# design.net
KiCad netlist of a schematic drawn in Altium Designer
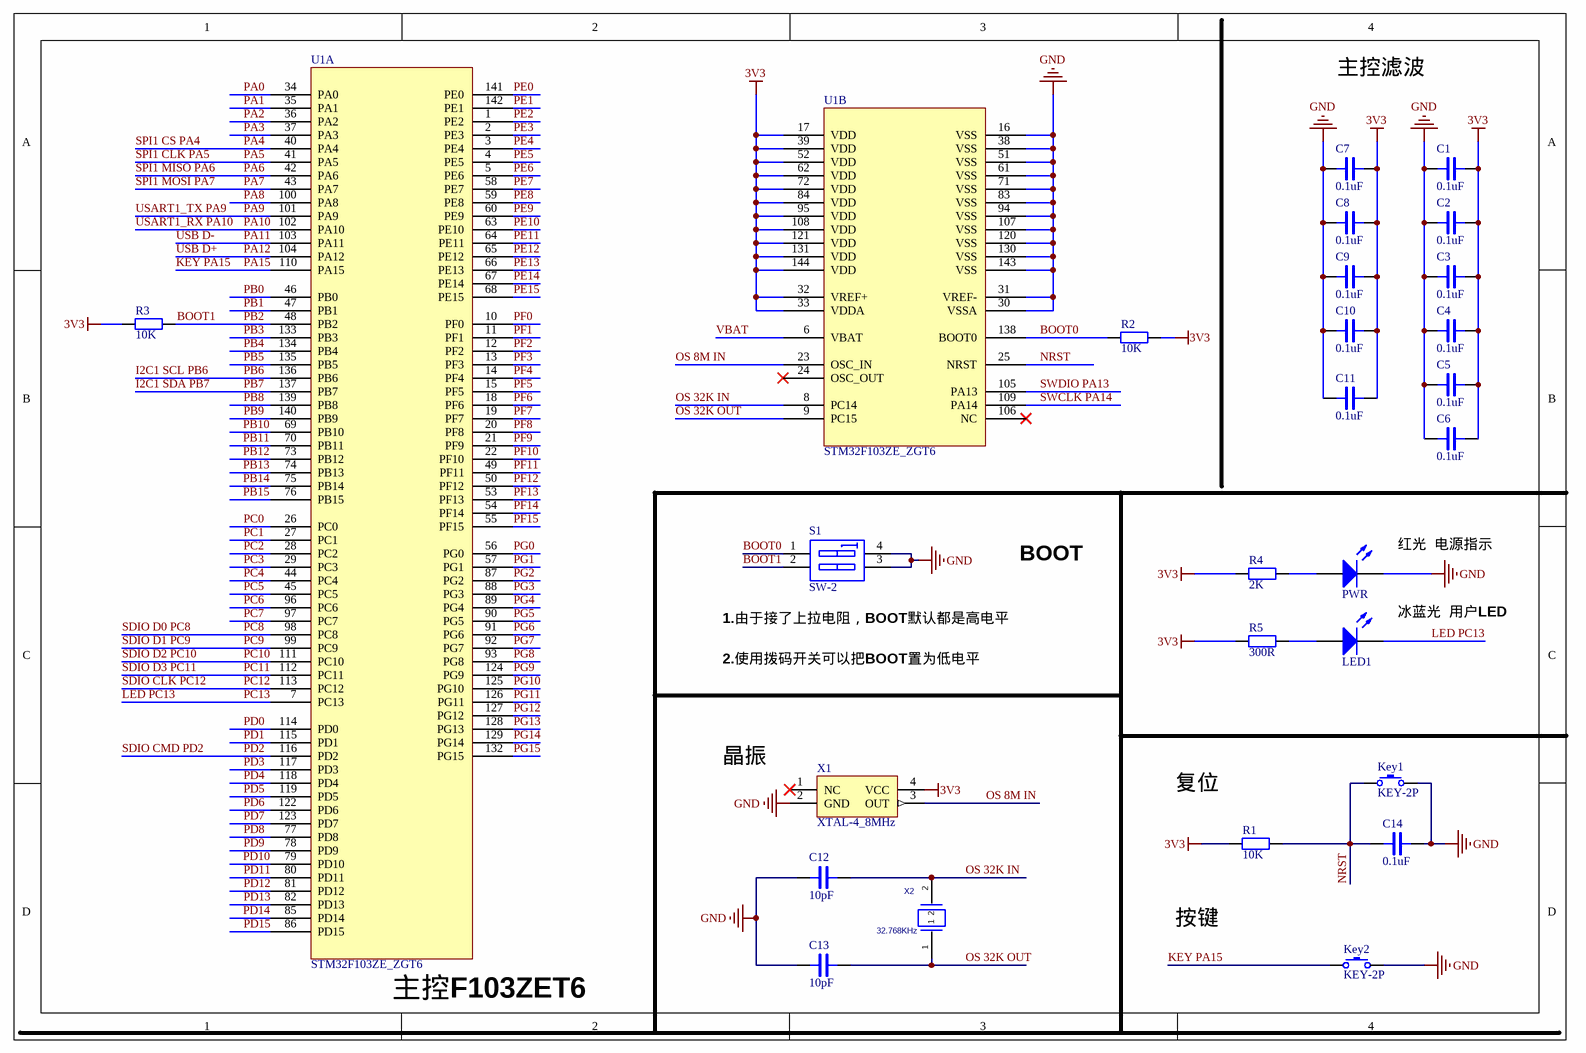
[diagram p0: 主控系统板.SchDoc]

(export (version "E")
  (design (tool "Eeschema 10.0.6"))
  (components
    (comp (ref "C1")
      (value "0.1uF")
      (footprint "0603")
      (description "Capacitor")
      (libsource (lib "General") (part "CAP"))
    )
    (comp (ref "C2")
      (value "0.1uF")
      (footprint "0603")
      (description "Capacitor")
      (libsource (lib "General") (part "CAP"))
    )
    (comp (ref "C3")
      (value "0.1uF")
      (footprint "0603")
      (description "Capacitor")
      (libsource (lib "General") (part "CAP"))
    )
    (comp (ref "C4")
      (value "0.1uF")
      (footprint "0603")
      (description "Capacitor")
      (libsource (lib "General") (part "CAP"))
    )
    (comp (ref "C5")
      (value "0.1uF")
      (footprint "0603")
      (description "Capacitor")
      (libsource (lib "General") (part "CAP"))
    )
    (comp (ref "C6")
      (value "0.1uF")
      (footprint "0603")
      (description "Capacitor")
      (libsource (lib "General") (part "CAP"))
    )
    (comp (ref "C7")
      (value "0.1uF")
      (footprint "0603")
      (description "Capacitor")
      (libsource (lib "General") (part "CAP"))
    )
    (comp (ref "C8")
      (value "0.1uF")
      (footprint "0603")
      (description "Capacitor")
      (libsource (lib "General") (part "CAP"))
    )
    (comp (ref "C9")
      (value "0.1uF")
      (footprint "0603")
      (description "Capacitor")
      (libsource (lib "General") (part "CAP"))
    )
    (comp (ref "C10")
      (value "0.1uF")
      (footprint "0603")
      (description "Capacitor")
      (libsource (lib "General") (part "CAP"))
    )
    (comp (ref "C11")
      (value "0.1uF")
      (footprint "0603")
      (description "Capacitor")
      (libsource (lib "General") (part "CAP"))
    )
    (comp (ref "C12")
      (value "10pF")
      (footprint "0603")
      (description "Capacitor")
      (libsource (lib "General") (part "CAP"))
    )
    (comp (ref "C13")
      (value "10pF")
      (footprint "0603")
      (description "Capacitor")
      (libsource (lib "General") (part "CAP"))
    )
    (comp (ref "C14")
      (value "0.1uF")
      (footprint "0603")
      (description "Capacitor")
      (libsource (lib "General") (part "CAP"))
    )
    (comp (ref "Key1")
      (value "KEY-2P")
      (footprint "TSW SMD-3*6*2.5")
      (description "Key")
      (libsource (lib "General") (part "KEY-2P"))
    )
    (comp (ref "Key2")
      (value "KEY-2P")
      (footprint "TSW SMD-3*6*2.5")
      (description "Key")
      (libsource (lib "General") (part "KEY-2P"))
    )
    (comp (ref "LED1")
      (value "LED")
      (footprint "D0603")
      (libsource (lib "altium-import") (part "root_0_LED_"))
    )
    (comp (ref "PWR")
      (value "LED")
      (footprint "D0603")
      (libsource (lib "altium-import") (part "root_0_LED_"))
    )
    (comp (ref "R1")
      (value "10K")
      (footprint "0603")
      (description "Resistor")
      (libsource (lib "") (part "RES_1"))
    )
    (comp (ref "R2")
      (value "10K")
      (footprint "0603")
      (description "Resistor")
      (libsource (lib "") (part "RES_1"))
    )
    (comp (ref "R3")
      (value "10K")
      (footprint "0603")
      (description "Resistor")
      (libsource (lib "General") (part "RES"))
    )
    (comp (ref "R4")
      (value "2K")
      (footprint "0603")
      (description "Resistor")
      (libsource (lib "General") (part "RES"))
    )
    (comp (ref "R5")
      (value "300R")
      (footprint "0603")
      (description "Resistor")
      (libsource (lib "General") (part "RES"))
    )
    (comp (ref "S1")
      (value "SW-2")
      (footprint "CSW1.27 SMD-2P")
      (libsource (lib "altium-import") (part "root_0_SW-2_"))
    )
    (comp (ref "U1")
      (value "STM32F103ZE_ZGT6")
      (footprint "TQFP144_N")
      (libsource (lib "altium-import") (part "root_0_STM32F103ZE_ZGT6_"))
    )
    (comp (ref "X1")
      (value "XTAL-4_8MHz")
      (footprint "XTAL-5.0X3.2")
      (description "Oscillator")
      (libsource (lib "General") (part "XTAL-4"))
    )
    (comp (ref "X2")
      (value "32.768KHz")
      (footprint "3215")
      (description "CRYSTAL")
      (fields (field (name "Comment") "XTAL_32.768KHZ_3215"))
      (libsource (lib "altium-import") (part "root_0_XTAL_32.768KHZ_3215_"))
    )
  )
  (nets
    (net (code "1") (name "/BOOT0") (class "Default")
      (node (ref "R2") (pin "1") (pinfunction "1_1") (pintype "passive"))
      (node (ref "S1") (pin "1") (pinfunction "A1_1") (pintype "passive"))
      (node (ref "U1") (pin "138") (pinfunction "BOOT0_138") (pintype "passive"))
    )
    (net (code "2") (name "/BOOT1") (class "Default")
      (node (ref "R3") (pin "1") (pinfunction "1_1") (pintype "passive"))
      (node (ref "S1") (pin "2") (pinfunction "A2_2") (pintype "passive"))
      (node (ref "U1") (pin "48") (pinfunction "PB2_48") (pintype "passive"))
    )
    (net (code "3") (name "/I2C1 SCL PB6") (class "Default")
      (node (ref "U1") (pin "136") (pinfunction "PB6_136") (pintype "passive"))
    )
    (net (code "4") (name "/I2C1 SDA PB7") (class "Default")
      (node (ref "U1") (pin "137") (pinfunction "PB7_137") (pintype "passive"))
    )
    (net (code "5") (name "/KEY PA15") (class "Default")
      (node (ref "Key2") (pin "1") (pinfunction "1_1") (pintype "passive"))
      (node (ref "U1") (pin "110") (pinfunction "PA15_110") (pintype "passive"))
    )
    (net (code "6") (name "/LED PC13") (class "Default")
      (node (ref "LED1") (pin "2") (pinfunction "K_2") (pintype "passive"))
      (node (ref "U1") (pin "7") (pinfunction "PC13_7") (pintype "passive"))
    )
    (net (code "7") (name "/NRST") (class "Default")
      (node (ref "C14") (pin "2") (pinfunction "2_2") (pintype "passive"))
      (node (ref "Key1") (pin "1") (pinfunction "1_1") (pintype "passive"))
      (node (ref "R1") (pin "2") (pinfunction "2_2") (pintype "passive"))
      (node (ref "U1") (pin "25") (pinfunction "NRST_25") (pintype "passive"))
    )
    (net (code "8") (name "/OS 8M IN") (class "Default")
      (node (ref "U1") (pin "23") (pinfunction "OSC_IN_23") (pintype "passive"))
      (node (ref "X1") (pin "3") (pinfunction "OUT_3") (pintype "output"))
    )
    (net (code "9") (name "/OS 32K IN") (class "Default")
      (node (ref "C12") (pin "1") (pinfunction "1_1") (pintype "passive"))
      (node (ref "U1") (pin "8") (pinfunction "PC14_8") (pintype "passive"))
      (node (ref "X2") (pin "2") (pinfunction "2_2") (pintype "passive"))
    )
    (net (code "10") (name "/OS 32K OUT") (class "Default")
      (node (ref "C13") (pin "1") (pinfunction "1_1") (pintype "passive"))
      (node (ref "U1") (pin "9") (pinfunction "PC15_9") (pintype "passive"))
      (node (ref "X2") (pin "1") (pinfunction "1_1") (pintype "passive"))
    )
    (net (code "11") (name "/PA0") (class "Default")
      (node (ref "U1") (pin "34") (pinfunction "PA0_34") (pintype "passive"))
    )
    (net (code "12") (name "/PA1") (class "Default")
      (node (ref "U1") (pin "35") (pinfunction "PA1_35") (pintype "passive"))
    )
    (net (code "13") (name "/PA2") (class "Default")
      (node (ref "U1") (pin "36") (pinfunction "PA2_36") (pintype "passive"))
    )
    (net (code "14") (name "/PA3") (class "Default")
      (node (ref "U1") (pin "37") (pinfunction "PA3_37") (pintype "passive"))
    )
    (net (code "15") (name "/PA4") (class "Default")
      (node (ref "U1") (pin "40") (pinfunction "PA4_40") (pintype "passive"))
    )
    (net (code "16") (name "/PA5") (class "Default")
      (node (ref "U1") (pin "41") (pinfunction "PA5_41") (pintype "passive"))
    )
    (net (code "17") (name "/PA6") (class "Default")
      (node (ref "U1") (pin "42") (pinfunction "PA6_42") (pintype "passive"))
    )
    (net (code "18") (name "/PA7") (class "Default")
      (node (ref "U1") (pin "43") (pinfunction "PA7_43") (pintype "passive"))
    )
    (net (code "19") (name "/PA8") (class "Default")
      (node (ref "U1") (pin "100") (pinfunction "PA8_100") (pintype "passive"))
    )
    (net (code "20") (name "/PA9") (class "Default")
      (node (ref "U1") (pin "101") (pinfunction "PA9_101") (pintype "passive"))
    )
    (net (code "21") (name "/PA10") (class "Default")
      (node (ref "U1") (pin "102") (pinfunction "PA10_102") (pintype "passive"))
    )
    (net (code "22") (name "/PA11") (class "Default")
      (node (ref "U1") (pin "103") (pinfunction "PA11_103") (pintype "passive"))
    )
    (net (code "23") (name "/PA12") (class "Default")
      (node (ref "U1") (pin "104") (pinfunction "PA12_104") (pintype "passive"))
    )
    (net (code "24") (name "/PB0") (class "Default")
      (node (ref "U1") (pin "46") (pinfunction "PB0_46") (pintype "passive"))
    )
    (net (code "25") (name "/PB1") (class "Default")
      (node (ref "U1") (pin "47") (pinfunction "PB1_47") (pintype "passive"))
    )
    (net (code "26") (name "/PB3") (class "Default")
      (node (ref "U1") (pin "133") (pinfunction "PB3_133") (pintype "passive"))
    )
    (net (code "27") (name "/PB4") (class "Default")
      (node (ref "U1") (pin "134") (pinfunction "PB4_134") (pintype "passive"))
    )
    (net (code "28") (name "/PB5") (class "Default")
      (node (ref "U1") (pin "135") (pinfunction "PB5_135") (pintype "passive"))
    )
    (net (code "29") (name "/PB8") (class "Default")
      (node (ref "U1") (pin "139") (pinfunction "PB8_139") (pintype "passive"))
    )
    (net (code "30") (name "/PB9") (class "Default")
      (node (ref "U1") (pin "140") (pinfunction "PB9_140") (pintype "passive"))
    )
    (net (code "31") (name "/PB10") (class "Default")
      (node (ref "U1") (pin "69") (pinfunction "PB10_69") (pintype "passive"))
    )
    (net (code "32") (name "/PB11") (class "Default")
      (node (ref "U1") (pin "70") (pinfunction "PB11_70") (pintype "passive"))
    )
    (net (code "33") (name "/PB12") (class "Default")
      (node (ref "U1") (pin "73") (pinfunction "PB12_73") (pintype "passive"))
    )
    (net (code "34") (name "/PB13") (class "Default")
      (node (ref "U1") (pin "74") (pinfunction "PB13_74") (pintype "passive"))
    )
    (net (code "35") (name "/PB14") (class "Default")
      (node (ref "U1") (pin "75") (pinfunction "PB14_75") (pintype "passive"))
    )
    (net (code "36") (name "/PB15") (class "Default")
      (node (ref "U1") (pin "76") (pinfunction "PB15_76") (pintype "passive"))
    )
    (net (code "37") (name "/PC0") (class "Default")
      (node (ref "U1") (pin "26") (pinfunction "PC0_26") (pintype "passive"))
    )
    (net (code "38") (name "/PC1") (class "Default")
      (node (ref "U1") (pin "27") (pinfunction "PC1_27") (pintype "passive"))
    )
    (net (code "39") (name "/PC2") (class "Default")
      (node (ref "U1") (pin "28") (pinfunction "PC2_28") (pintype "passive"))
    )
    (net (code "40") (name "/PC3") (class "Default")
      (node (ref "U1") (pin "29") (pinfunction "PC3_29") (pintype "passive"))
    )
    (net (code "41") (name "/PC4") (class "Default")
      (node (ref "U1") (pin "44") (pinfunction "PC4_44") (pintype "passive"))
    )
    (net (code "42") (name "/PC5") (class "Default")
      (node (ref "U1") (pin "45") (pinfunction "PC5_45") (pintype "passive"))
    )
    (net (code "43") (name "/PC6") (class "Default")
      (node (ref "U1") (pin "96") (pinfunction "PC6_96") (pintype "passive"))
    )
    (net (code "44") (name "/PC7") (class "Default")
      (node (ref "U1") (pin "97") (pinfunction "PC7_97") (pintype "passive"))
    )
    (net (code "45") (name "/PC8") (class "Default")
      (node (ref "U1") (pin "98") (pinfunction "PC8_98") (pintype "passive"))
    )
    (net (code "46") (name "/PC9") (class "Default")
      (node (ref "U1") (pin "99") (pinfunction "PC9_99") (pintype "passive"))
    )
    (net (code "47") (name "/PC10") (class "Default")
      (node (ref "U1") (pin "111") (pinfunction "PC10_111") (pintype "passive"))
    )
    (net (code "48") (name "/PC11") (class "Default")
      (node (ref "U1") (pin "112") (pinfunction "PC11_112") (pintype "passive"))
    )
    (net (code "49") (name "/PC12") (class "Default")
      (node (ref "U1") (pin "113") (pinfunction "PC12_113") (pintype "passive"))
    )
    (net (code "50") (name "/PD0") (class "Default")
      (node (ref "U1") (pin "114") (pinfunction "PD0_114") (pintype "passive"))
    )
    (net (code "51") (name "/PD1") (class "Default")
      (node (ref "U1") (pin "115") (pinfunction "PD1_115") (pintype "passive"))
    )
    (net (code "52") (name "/PD2") (class "Default")
      (node (ref "U1") (pin "116") (pinfunction "PD2_116") (pintype "passive"))
    )
    (net (code "53") (name "/PD3") (class "Default")
      (node (ref "U1") (pin "117") (pinfunction "PD3_117") (pintype "passive"))
    )
    (net (code "54") (name "/PD4") (class "Default")
      (node (ref "U1") (pin "118") (pinfunction "PD4_118") (pintype "passive"))
    )
    (net (code "55") (name "/PD5") (class "Default")
      (node (ref "U1") (pin "119") (pinfunction "PD5_119") (pintype "passive"))
    )
    (net (code "56") (name "/PD6") (class "Default")
      (node (ref "U1") (pin "122") (pinfunction "PD6_122") (pintype "passive"))
    )
    (net (code "57") (name "/PD7") (class "Default")
      (node (ref "U1") (pin "123") (pinfunction "PD7_123") (pintype "passive"))
    )
    (net (code "58") (name "/PD8") (class "Default")
      (node (ref "U1") (pin "77") (pinfunction "PD8_77") (pintype "passive"))
    )
    (net (code "59") (name "/PD9") (class "Default")
      (node (ref "U1") (pin "78") (pinfunction "PD9_78") (pintype "passive"))
    )
    (net (code "60") (name "/PD10") (class "Default")
      (node (ref "U1") (pin "79") (pinfunction "PD10_79") (pintype "passive"))
    )
    (net (code "61") (name "/PD11") (class "Default")
      (node (ref "U1") (pin "80") (pinfunction "PD11_80") (pintype "passive"))
    )
    (net (code "62") (name "/PD12") (class "Default")
      (node (ref "U1") (pin "81") (pinfunction "PD12_81") (pintype "passive"))
    )
    (net (code "63") (name "/PD13") (class "Default")
      (node (ref "U1") (pin "82") (pinfunction "PD13_82") (pintype "passive"))
    )
    (net (code "64") (name "/PD14") (class "Default")
      (node (ref "U1") (pin "85") (pinfunction "PD14_85") (pintype "passive"))
    )
    (net (code "65") (name "/PD15") (class "Default")
      (node (ref "U1") (pin "86") (pinfunction "PD15_86") (pintype "passive"))
    )
    (net (code "66") (name "/PE0") (class "Default")
      (node (ref "U1") (pin "141") (pinfunction "PE0_141") (pintype "passive"))
    )
    (net (code "67") (name "/PE1") (class "Default")
      (node (ref "U1") (pin "142") (pinfunction "PE1_142") (pintype "passive"))
    )
    (net (code "68") (name "/PE2") (class "Default")
      (node (ref "U1") (pin "1") (pinfunction "PE2_1") (pintype "passive"))
    )
    (net (code "69") (name "/PE3") (class "Default")
      (node (ref "U1") (pin "2") (pinfunction "PE3_2") (pintype "passive"))
    )
    (net (code "70") (name "/PE4") (class "Default")
      (node (ref "U1") (pin "3") (pinfunction "PE4_3") (pintype "passive"))
    )
    (net (code "71") (name "/PE5") (class "Default")
      (node (ref "U1") (pin "4") (pinfunction "PE5_4") (pintype "passive"))
    )
    (net (code "72") (name "/PE6") (class "Default")
      (node (ref "U1") (pin "5") (pinfunction "PE6_5") (pintype "passive"))
    )
    (net (code "73") (name "/PE7") (class "Default")
      (node (ref "U1") (pin "58") (pinfunction "PE7_58") (pintype "passive"))
    )
    (net (code "74") (name "/PE8") (class "Default")
      (node (ref "U1") (pin "59") (pinfunction "PE8_59") (pintype "passive"))
    )
    (net (code "75") (name "/PE9") (class "Default")
      (node (ref "U1") (pin "60") (pinfunction "PE9_60") (pintype "passive"))
    )
    (net (code "76") (name "/PE10") (class "Default")
      (node (ref "U1") (pin "63") (pinfunction "PE10_63") (pintype "passive"))
    )
    (net (code "77") (name "/PE11") (class "Default")
      (node (ref "U1") (pin "64") (pinfunction "PE11_64") (pintype "passive"))
    )
    (net (code "78") (name "/PE12") (class "Default")
      (node (ref "U1") (pin "65") (pinfunction "PE12_65") (pintype "passive"))
    )
    (net (code "79") (name "/PE13") (class "Default")
      (node (ref "U1") (pin "66") (pinfunction "PE13_66") (pintype "passive"))
    )
    (net (code "80") (name "/PE14") (class "Default")
      (node (ref "U1") (pin "67") (pinfunction "PE14_67") (pintype "passive"))
    )
    (net (code "81") (name "/PE15") (class "Default")
      (node (ref "U1") (pin "68") (pinfunction "PE15_68") (pintype "passive"))
    )
    (net (code "82") (name "/PF0") (class "Default")
      (node (ref "U1") (pin "10") (pinfunction "PF0_10") (pintype "passive"))
    )
    (net (code "83") (name "/PF1") (class "Default")
      (node (ref "U1") (pin "11") (pinfunction "PF1_11") (pintype "passive"))
    )
    (net (code "84") (name "/PF2") (class "Default")
      (node (ref "U1") (pin "12") (pinfunction "PF2_12") (pintype "passive"))
    )
    (net (code "85") (name "/PF3") (class "Default")
      (node (ref "U1") (pin "13") (pinfunction "PF3_13") (pintype "passive"))
    )
    (net (code "86") (name "/PF4") (class "Default")
      (node (ref "U1") (pin "14") (pinfunction "PF4_14") (pintype "passive"))
    )
    (net (code "87") (name "/PF5") (class "Default")
      (node (ref "U1") (pin "15") (pinfunction "PF5_15") (pintype "passive"))
    )
    (net (code "88") (name "/PF6") (class "Default")
      (node (ref "U1") (pin "18") (pinfunction "PF6_18") (pintype "passive"))
    )
    (net (code "89") (name "/PF7") (class "Default")
      (node (ref "U1") (pin "19") (pinfunction "PF7_19") (pintype "passive"))
    )
    (net (code "90") (name "/PF8") (class "Default")
      (node (ref "U1") (pin "20") (pinfunction "PF8_20") (pintype "passive"))
    )
    (net (code "91") (name "/PF9") (class "Default")
      (node (ref "U1") (pin "21") (pinfunction "PF9_21") (pintype "passive"))
    )
    (net (code "92") (name "/PF10") (class "Default")
      (node (ref "U1") (pin "22") (pinfunction "PF10_22") (pintype "passive"))
    )
    (net (code "93") (name "/PF11") (class "Default")
      (node (ref "U1") (pin "49") (pinfunction "PF11_49") (pintype "passive"))
    )
    (net (code "94") (name "/PF12") (class "Default")
      (node (ref "U1") (pin "50") (pinfunction "PF12_50") (pintype "passive"))
    )
    (net (code "95") (name "/PF13") (class "Default")
      (node (ref "U1") (pin "53") (pinfunction "PF13_53") (pintype "passive"))
    )
    (net (code "96") (name "/PF14") (class "Default")
      (node (ref "U1") (pin "54") (pinfunction "PF14_54") (pintype "passive"))
    )
    (net (code "97") (name "/PF15") (class "Default")
      (node (ref "U1") (pin "55") (pinfunction "PF15_55") (pintype "passive"))
    )
    (net (code "98") (name "/PG0") (class "Default")
      (node (ref "U1") (pin "56") (pinfunction "PG0_56") (pintype "passive"))
    )
    (net (code "99") (name "/PG1") (class "Default")
      (node (ref "U1") (pin "57") (pinfunction "PG1_57") (pintype "passive"))
    )
    (net (code "100") (name "/PG2") (class "Default")
      (node (ref "U1") (pin "87") (pinfunction "PG2_87") (pintype "passive"))
    )
    (net (code "101") (name "/PG3") (class "Default")
      (node (ref "U1") (pin "88") (pinfunction "PG3_88") (pintype "passive"))
    )
    (net (code "102") (name "/PG4") (class "Default")
      (node (ref "U1") (pin "89") (pinfunction "PG4_89") (pintype "passive"))
    )
    (net (code "103") (name "/PG5") (class "Default")
      (node (ref "U1") (pin "90") (pinfunction "PG5_90") (pintype "passive"))
    )
    (net (code "104") (name "/PG6") (class "Default")
      (node (ref "U1") (pin "91") (pinfunction "PG6_91") (pintype "passive"))
    )
    (net (code "105") (name "/PG7") (class "Default")
      (node (ref "U1") (pin "92") (pinfunction "PG7_92") (pintype "passive"))
    )
    (net (code "106") (name "/PG8") (class "Default")
      (node (ref "U1") (pin "93") (pinfunction "PG8_93") (pintype "passive"))
    )
    (net (code "107") (name "/PG9") (class "Default")
      (node (ref "U1") (pin "124") (pinfunction "PG9_124") (pintype "passive"))
    )
    (net (code "108") (name "/PG10") (class "Default")
      (node (ref "U1") (pin "125") (pinfunction "PG10_125") (pintype "passive"))
    )
    (net (code "109") (name "/PG11") (class "Default")
      (node (ref "U1") (pin "126") (pinfunction "PG11_126") (pintype "passive"))
    )
    (net (code "110") (name "/PG12") (class "Default")
      (node (ref "U1") (pin "127") (pinfunction "PG12_127") (pintype "passive"))
    )
    (net (code "111") (name "/PG13") (class "Default")
      (node (ref "U1") (pin "128") (pinfunction "PG13_128") (pintype "passive"))
    )
    (net (code "112") (name "/PG14") (class "Default")
      (node (ref "U1") (pin "129") (pinfunction "PG14_129") (pintype "passive"))
    )
    (net (code "113") (name "/PG15") (class "Default")
      (node (ref "U1") (pin "132") (pinfunction "PG15_132") (pintype "passive"))
    )
    (net (code "114") (name "/SWCLK PA14") (class "Default")
      (node (ref "U1") (pin "109") (pinfunction "PA14_109") (pintype "passive"))
    )
    (net (code "115") (name "/SWDIO PA13") (class "Default")
      (node (ref "U1") (pin "105") (pinfunction "PA13_105") (pintype "passive"))
    )
    (net (code "116") (name "/VBAT") (class "Default")
      (node (ref "U1") (pin "6") (pinfunction "VBAT_6") (pintype "passive"))
    )
    (net (code "117") (name "3V3") (class "Default")
      (node (ref "C1") (pin "2") (pinfunction "2_2") (pintype "passive"))
      (node (ref "C10") (pin "2") (pinfunction "2_2") (pintype "passive"))
      (node (ref "C11") (pin "2") (pinfunction "2_2") (pintype "passive"))
      (node (ref "C2") (pin "2") (pinfunction "2_2") (pintype "passive"))
      (node (ref "C3") (pin "2") (pinfunction "2_2") (pintype "passive"))
      (node (ref "C4") (pin "2") (pinfunction "2_2") (pintype "passive"))
      (node (ref "C5") (pin "2") (pinfunction "2_2") (pintype "passive"))
      (node (ref "C6") (pin "2") (pinfunction "2_2") (pintype "passive"))
      (node (ref "C7") (pin "2") (pinfunction "2_2") (pintype "passive"))
      (node (ref "C8") (pin "2") (pinfunction "2_2") (pintype "passive"))
      (node (ref "C9") (pin "2") (pinfunction "2_2") (pintype "passive"))
      (node (ref "R1") (pin "1") (pinfunction "1_1") (pintype "passive"))
      (node (ref "R2") (pin "2") (pinfunction "2_2") (pintype "passive"))
      (node (ref "R3") (pin "2") (pinfunction "2_2") (pintype "passive"))
      (node (ref "R4") (pin "2") (pinfunction "2_2") (pintype "passive"))
      (node (ref "R5") (pin "2") (pinfunction "2_2") (pintype "passive"))
      (node (ref "U1") (pin "108") (pinfunction "VDD_108") (pintype "passive"))
      (node (ref "U1") (pin "121") (pinfunction "VDD_121") (pintype "passive"))
      (node (ref "U1") (pin "131") (pinfunction "VDD_131") (pintype "passive"))
      (node (ref "U1") (pin "144") (pinfunction "VDD_144") (pintype "passive"))
      (node (ref "U1") (pin "17") (pinfunction "VDD_17") (pintype "passive"))
      (node (ref "U1") (pin "32") (pinfunction "VREF+_32") (pintype "passive"))
      (node (ref "U1") (pin "33") (pinfunction "VDDA_33") (pintype "passive"))
      (node (ref "U1") (pin "39") (pinfunction "VDD_39") (pintype "passive"))
      (node (ref "U1") (pin "52") (pinfunction "VDD_52") (pintype "passive"))
      (node (ref "U1") (pin "62") (pinfunction "VDD_62") (pintype "passive"))
      (node (ref "U1") (pin "72") (pinfunction "VDD_72") (pintype "passive"))
      (node (ref "U1") (pin "84") (pinfunction "VDD_84") (pintype "passive"))
      (node (ref "U1") (pin "95") (pinfunction "VDD_95") (pintype "passive"))
      (node (ref "X1") (pin "4") (pinfunction "VCC_4") (pintype "power_in"))
    )
    (net (code "118") (name "GND") (class "Default")
      (node (ref "C1") (pin "1") (pinfunction "1_1") (pintype "passive"))
      (node (ref "C10") (pin "1") (pinfunction "1_1") (pintype "passive"))
      (node (ref "C11") (pin "1") (pinfunction "1_1") (pintype "passive"))
      (node (ref "C12") (pin "2") (pinfunction "2_2") (pintype "passive"))
      (node (ref "C13") (pin "2") (pinfunction "2_2") (pintype "passive"))
      (node (ref "C14") (pin "1") (pinfunction "1_1") (pintype "passive"))
      (node (ref "C2") (pin "1") (pinfunction "1_1") (pintype "passive"))
      (node (ref "C3") (pin "1") (pinfunction "1_1") (pintype "passive"))
      (node (ref "C4") (pin "1") (pinfunction "1_1") (pintype "passive"))
      (node (ref "C5") (pin "1") (pinfunction "1_1") (pintype "passive"))
      (node (ref "C6") (pin "1") (pinfunction "1_1") (pintype "passive"))
      (node (ref "C7") (pin "1") (pinfunction "1_1") (pintype "passive"))
      (node (ref "C8") (pin "1") (pinfunction "1_1") (pintype "passive"))
      (node (ref "C9") (pin "1") (pinfunction "1_1") (pintype "passive"))
      (node (ref "Key1") (pin "2") (pinfunction "2_2") (pintype "passive"))
      (node (ref "Key2") (pin "2") (pinfunction "2_2") (pintype "passive"))
      (node (ref "PWR") (pin "2") (pinfunction "K_2") (pintype "passive"))
      (node (ref "S1") (pin "3") (pinfunction "B2_3") (pintype "passive"))
      (node (ref "S1") (pin "4") (pinfunction "B1_4") (pintype "passive"))
      (node (ref "U1") (pin "107") (pinfunction "VSS_107") (pintype "passive"))
      (node (ref "U1") (pin "120") (pinfunction "VSS_120") (pintype "passive"))
      (node (ref "U1") (pin "130") (pinfunction "VSS_130") (pintype "passive"))
      (node (ref "U1") (pin "143") (pinfunction "VSS_143") (pintype "passive"))
      (node (ref "U1") (pin "16") (pinfunction "VSS_16") (pintype "passive"))
      (node (ref "U1") (pin "30") (pinfunction "VSSA_30") (pintype "passive"))
      (node (ref "U1") (pin "31") (pinfunction "VREF-_31") (pintype "passive"))
      (node (ref "U1") (pin "38") (pinfunction "VSS_38") (pintype "passive"))
      (node (ref "U1") (pin "51") (pinfunction "VSS_51") (pintype "passive"))
      (node (ref "U1") (pin "61") (pinfunction "VSS_61") (pintype "passive"))
      (node (ref "U1") (pin "71") (pinfunction "VSS_71") (pintype "passive"))
      (node (ref "U1") (pin "83") (pinfunction "VSS_83") (pintype "passive"))
      (node (ref "U1") (pin "94") (pinfunction "VSS_94") (pintype "passive"))
      (node (ref "X1") (pin "2") (pinfunction "GND_2") (pintype "power_in"))
    )
    (net (code "119") (name "Net-(LED1-A)") (class "Default")
      (node (ref "LED1") (pin "1") (pinfunction "A_1") (pintype "passive"))
      (node (ref "R5") (pin "1") (pinfunction "1_1") (pintype "passive"))
    )
    (net (code "120") (name "Net-(PWR-A)") (class "Default")
      (node (ref "PWR") (pin "1") (pinfunction "A_1") (pintype "passive"))
      (node (ref "R4") (pin "1") (pinfunction "1_1") (pintype "passive"))
    )
    (net (code "121") (name "unconnected-(U1B-NC-Pad106)") (class "Default")
      (node (ref "U1") (pin "106") (pinfunction "NC_106") (pintype "passive+no_connect"))
    )
    (net (code "122") (name "unconnected-(U1B-OSC_OUT-Pad24)") (class "Default")
      (node (ref "U1") (pin "24") (pinfunction "OSC_OUT_24") (pintype "passive+no_connect"))
    )
    (net (code "123") (name "unconnected-(X1-NC-Pad1)") (class "Default")
      (node (ref "X1") (pin "1") (pinfunction "NC_1") (pintype "passive+no_connect"))
    )
  )
)
